# pH.net
KiCad netlist of a schematic drawn in Altium Designer
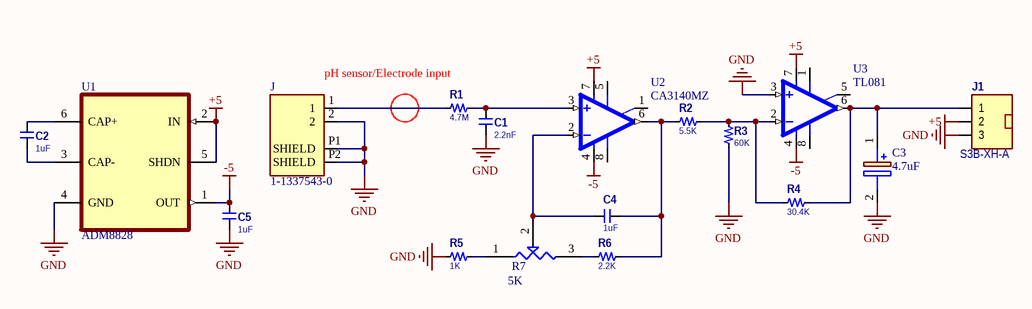
[diagram p0: pH.SchDoc]

(export (version "E")
  (design (tool "Eeschema 10.0.6"))
  (components
    (comp (ref "C1")
      (value "2.2nF")
      (footprint "0805-C_N")
      (description "CAP CER 1000PF 50V X7R 0805")
      (fields
        (field (name "MANUFACTURER") "Panasonic")
        (field (name "MANUFACTURER PART NUMBER") "ECJ2VB1H102K")
      )
      (libsource (lib "Capacitors") (part "CAP CER 1000PF 50V X7R 0805_(F5.1.2)"))
    )
    (comp (ref "C2")
      (value "1uF")
      (footprint "0805-C_N")
      (description "CAP CER 1000PF 50V X7R 0805")
      (fields
        (field (name "MANUFACTURER") "Panasonic")
        (field (name "MANUFACTURER PART NUMBER") "ECJ2VB1H102K")
      )
      (libsource (lib "Capacitors") (part "CAP CER 1000PF 50V X7R 0805_(F5.1.2)"))
    )
    (comp (ref "C3")
      (value "4.7uF")
      (footprint "CAPPM7344X430N")
      (description "Capacitor Polarised")
      (fields
        (field (name "MANUFACTURER_PART_NUMBER") "TAJE227K010RNJ")
        (field (name "MOUSER PART NUMBER") "581-TAJE227K010R")
      )
      (libsource (lib "AC_Voice_Module_") (part "220 uf Tantalun"))
    )
    (comp (ref "C4")
      (value "1uF")
      (footprint "0805-C_N")
      (description "CAP CER 1000PF 50V X7R 0805")
      (fields
        (field (name "MANUFACTURER") "Panasonic")
        (field (name "MANUFACTURER PART NUMBER") "ECJ2VB1H102K")
      )
      (libsource (lib "Capacitors") (part "CAP CER 1000PF 50V X7R 0805_(F5.1.2)"))
    )
    (comp (ref "C5")
      (value "1uF")
      (footprint "0805-C_N")
      (description "CAP CER 1000PF 50V X7R 0805")
      (fields
        (field (name "MANUFACTURER") "Panasonic")
        (field (name "MANUFACTURER PART NUMBER") "ECJ2VB1H102K")
      )
      (libsource (lib "Capacitors") (part "CAP CER 1000PF 50V X7R 0805_(F5.1.2)"))
    )
    (comp (ref "J")
      (value "1-1337543-0")
      (footprint "CONN_1-1337543-0")
      (description "Conn ZDC/BNC RCP 0Hz to 4GHz 50Ohm Solder RA Thru-Hole Gold Over Nickel Over Copper Individual")
      (fields (field (name "MF") "TE Connectivity"))
      (libsource (lib "Crops_Predictor") (part "1-1337543-0"))
    )
    (comp (ref "J1")
      (value "S3B-XH-A")
      (footprint "CON_HDR1x3_2p50_RA_SHRD_JST-S3B-XH-A")
      (description "Conn Shrouded Header (4 Sides) HDR 3 POS 2.5mm Solder RA Side Entry Thru-Hole Box")
      (fields
        (field (name "MANUFACTURER") "JST")
        (field (name "MANUFACTURER PART NUMBER") "S3B-XH-A(LF)(SN)")
      )
      (libsource (lib "Connectors") (part "CON_HDR1x3_2p50_RA_SHRD_JST_S3B-XH-A"))
    )
    (comp (ref "R1")
      (value "4.7M")
      (footprint "0603-R_N")
      (description "11 kOhms ±1% 0.1W, 1/10W Chip Resistor 0603 (1608 Metric) Automotive AEC-Q200 Thick Film")
      (fields
        (field (name "MANUFACTURER") "Panasonic")
        (field (name "MANUFACTURER PART NUMBER") "ERJ-3EKF1102V")
      )
      (libsource (lib "Resistors") (part "R_11K OHM 1% 1/10W 0603"))
    )
    (comp (ref "R2")
      (value "5.5K")
      (footprint "0603-R_N")
      (description "11 kOhms ±1% 0.1W, 1/10W Chip Resistor 0603 (1608 Metric) Automotive AEC-Q200 Thick Film")
      (fields
        (field (name "MANUFACTURER") "Panasonic")
        (field (name "MANUFACTURER PART NUMBER") "ERJ-3EKF1102V")
      )
      (libsource (lib "Resistors") (part "R_11K OHM 1% 1/10W 0603"))
    )
    (comp (ref "R3")
      (value "60K")
      (footprint "0603-R_N")
      (description "11 kOhms ±1% 0.1W, 1/10W Chip Resistor 0603 (1608 Metric) Automotive AEC-Q200 Thick Film")
      (fields
        (field (name "MANUFACTURER") "Panasonic")
        (field (name "MANUFACTURER PART NUMBER") "ERJ-3EKF1102V")
      )
      (libsource (lib "Resistors") (part "R_11K OHM 1% 1/10W 0603"))
    )
    (comp (ref "R4")
      (value "30.4K")
      (footprint "0603-R_N")
      (description "11 kOhms ±1% 0.1W, 1/10W Chip Resistor 0603 (1608 Metric) Automotive AEC-Q200 Thick Film")
      (fields
        (field (name "MANUFACTURER") "Panasonic")
        (field (name "MANUFACTURER PART NUMBER") "ERJ-3EKF1102V")
      )
      (libsource (lib "Resistors") (part "R_11K OHM 1% 1/10W 0603"))
    )
    (comp (ref "R5")
      (value "1K")
      (footprint "0603-R_N")
      (description "11 kOhms ±1% 0.1W, 1/10W Chip Resistor 0603 (1608 Metric) Automotive AEC-Q200 Thick Film")
      (fields
        (field (name "MANUFACTURER") "Panasonic")
        (field (name "MANUFACTURER PART NUMBER") "ERJ-3EKF1102V")
      )
      (libsource (lib "Resistors") (part "R_11K OHM 1% 1/10W 0603"))
    )
    (comp (ref "R6")
      (value "2.2K")
      (footprint "0603-R_N")
      (description "11 kOhms ±1% 0.1W, 1/10W Chip Resistor 0603 (1608 Metric) Automotive AEC-Q200 Thick Film")
      (fields
        (field (name "MANUFACTURER") "Panasonic")
        (field (name "MANUFACTURER PART NUMBER") "ERJ-3EKF1102V")
      )
      (libsource (lib "Resistors") (part "R_11K OHM 1% 1/10W 0603"))
    )
    (comp (ref "R7")
      (value "5K")
      (footprint "TRIM_PV37W502C01B00")
      (fields (field (name "MF") "Murata Electronics") (field (name "MP") "PV37W502C01B00"))
      (libsource (lib "Crops_Predictor") (part "PV37W502C01B00"))
    )
    (comp (ref "U1")
      (value "ADM8828")
      (footprint "SOT-23-6")
      (description "Switched-Capacitor\r\nVoltage Inverter with Shutdown")
      (fields (field (name "MF") "Analog Devices"))
      (libsource (lib "Crops_Predictor") (part "ADM8828"))
    )
    (comp (ref "U2")
      (value "CA3140MZ")
      (footprint "SOIC127P600X175-8N")
      (description "General Purpose Amplifier 1 Circuit 8-SOIC")
      (fields (field (name "MF") "Renesas Electronics"))
      (libsource (lib "Crops_Predictor") (part "CA3140MZ"))
    )
    (comp (ref "U3")
      (value "TL081")
      (footprint "SOIC127P600X175-8N")
      (description "J-FET Amplifier 1 Circuit - 8-SOIC")
      (fields (field (name "MF") "STMicroelectronics"))
      (libsource (lib "Crops_Predictor") (part "TL081"))
    )
  )
  (nets
    (net (code "1") (name "+5") (class "Default")
      (node (ref "J1") (pin "2") (pinfunction "2_2") (pintype "passive"))
      (node (ref "U1") (pin "2") (pinfunction "IN_2") (pintype "input"))
      (node (ref "U1") (pin "5") (pinfunction "SHDN_5") (pintype "power_in"))
      (node (ref "U2") (pin "7") (pinfunction "V+_7") (pintype "power_in"))
      (node (ref "U3") (pin "7") (pinfunction "V+_7") (pintype "power_in"))
    )
    (net (code "2") (name "-5") (class "Default")
      (node (ref "C5") (pin "1") (pinfunction "1_1") (pintype "passive"))
      (node (ref "U1") (pin "1") (pinfunction "OUT_1") (pintype "output"))
      (node (ref "U2") (pin "4") (pinfunction "V-_4") (pintype "power_in"))
      (node (ref "U3") (pin "4") (pinfunction "V-_4") (pintype "power_in"))
    )
    (net (code "3") (name "GND") (class "Default")
      (node (ref "C1") (pin "2") (pinfunction "2_2") (pintype "passive"))
      (node (ref "C3") (pin "2") (pinfunction "-_2") (pintype "passive"))
      (node (ref "C5") (pin "2") (pinfunction "2_2") (pintype "passive"))
      (node (ref "J") (pin "2") (pinfunction "2_2") (pintype "passive"))
      (node (ref "J") (pin "P1") (pinfunction "SHIELD_P1") (pintype "passive"))
      (node (ref "J") (pin "P2") (pinfunction "SHIELD_P2") (pintype "passive"))
      (node (ref "J1") (pin "3") (pinfunction "3_3") (pintype "passive"))
      (node (ref "R3") (pin "1") (pinfunction "1_1") (pintype "passive"))
      (node (ref "R5") (pin "1") (pinfunction "1_1") (pintype "passive"))
      (node (ref "U1") (pin "4") (pinfunction "GND_4") (pintype "power_in"))
      (node (ref "U3") (pin "3") (pinfunction "+IN_3") (pintype "input"))
    )
    (net (code "4") (name "Net-(C3-+)") (class "Default")
      (node (ref "C3") (pin "1") (pinfunction "+_1") (pintype "passive"))
      (node (ref "J1") (pin "1") (pinfunction "1_1") (pintype "passive"))
      (node (ref "R4") (pin "2") (pinfunction "2_2") (pintype "passive"))
      (node (ref "U3") (pin "6") (pinfunction "OUT_6") (pintype "output"))
    )
    (net (code "5") (name "Net-(J-Pad1)") (class "Default")
      (node (ref "J") (pin "1") (pinfunction "1_1") (pintype "passive"))
      (node (ref "R1") (pin "1") (pinfunction "1_1") (pintype "passive"))
    )
    (net (code "6") (name "Net-(R5-Pad2)") (class "Default")
      (node (ref "R5") (pin "2") (pinfunction "2_2") (pintype "passive"))
      (node (ref "R7") (pin "1") (pinfunction "1_1") (pintype "passive"))
    )
    (net (code "7") (name "Net-(R6-Pad1)") (class "Default")
      (node (ref "R6") (pin "1") (pinfunction "1_1") (pintype "passive"))
      (node (ref "R7") (pin "3") (pinfunction "3_3") (pintype "passive"))
    )
    (net (code "8") (name "Net-(U1-CAP+)") (class "Default")
      (node (ref "C2") (pin "1") (pinfunction "1_1") (pintype "passive"))
      (node (ref "U1") (pin "6") (pinfunction "CAP+_6") (pintype "passive"))
    )
    (net (code "9") (name "Net-(U1-CAP-)") (class "Default")
      (node (ref "C2") (pin "2") (pinfunction "2_2") (pintype "passive"))
      (node (ref "U1") (pin "3") (pinfunction "CAP-_3") (pintype "passive"))
    )
    (net (code "10") (name "Net-(U2-+IN)") (class "Default")
      (node (ref "C1") (pin "1") (pinfunction "1_1") (pintype "passive"))
      (node (ref "R1") (pin "2") (pinfunction "2_2") (pintype "passive"))
      (node (ref "U2") (pin "3") (pinfunction "+IN_3") (pintype "input"))
    )
    (net (code "11") (name "Net-(U2--IN)") (class "Default")
      (node (ref "C4") (pin "1") (pinfunction "1_1") (pintype "passive"))
      (node (ref "R7") (pin "2") (pinfunction "2_2") (pintype "passive"))
      (node (ref "U2") (pin "2") (pinfunction "-IN_2") (pintype "input"))
    )
    (net (code "12") (name "Net-(U2-OUT)") (class "Default")
      (node (ref "C4") (pin "2") (pinfunction "2_2") (pintype "passive"))
      (node (ref "R2") (pin "1") (pinfunction "1_1") (pintype "passive"))
      (node (ref "R6") (pin "2") (pinfunction "2_2") (pintype "passive"))
      (node (ref "U2") (pin "6") (pinfunction "OUT_6") (pintype "output"))
    )
    (net (code "13") (name "Net-(U3--IN)") (class "Default")
      (node (ref "R2") (pin "2") (pinfunction "2_2") (pintype "passive"))
      (node (ref "R3") (pin "2") (pinfunction "2_2") (pintype "passive"))
      (node (ref "R4") (pin "1") (pinfunction "1_1") (pintype "passive"))
      (node (ref "U3") (pin "2") (pinfunction "-IN_2") (pintype "input"))
    )
    (net (code "14") (name "unconnected-(U2-CMP-Pad8)") (class "Default")
      (node (ref "U2") (pin "8") (pinfunction "CMP_8") (pintype "passive"))
    )
    (net (code "15") (name "unconnected-(U2-ON-Pad5)") (class "Default")
      (node (ref "U2") (pin "5") (pinfunction "ON_5") (pintype "passive"))
    )
    (net (code "16") (name "unconnected-(U2-ON{slash}CMP-Pad1)") (class "Default")
      (node (ref "U2") (pin "1") (pinfunction "ON/CMP_1") (pintype "passive"))
    )
    (net (code "17") (name "unconnected-(U3-ON1-Pad1)") (class "Default")
      (node (ref "U3") (pin "1") (pinfunction "ON1_1") (pintype "passive"))
    )
    (net (code "18") (name "unconnected-(U3-ON2-Pad5)") (class "Default")
      (node (ref "U3") (pin "5") (pinfunction "ON2_5") (pintype "passive"))
    )
    (net (code "19") (name "unconnected-(U3-OPT-Pad8)") (class "Default")
      (node (ref "U3") (pin "8") (pinfunction "OPT_8") (pintype "passive"))
    )
  )
)
